# MCU.net
KiCad netlist of a schematic drawn in Altium Designer
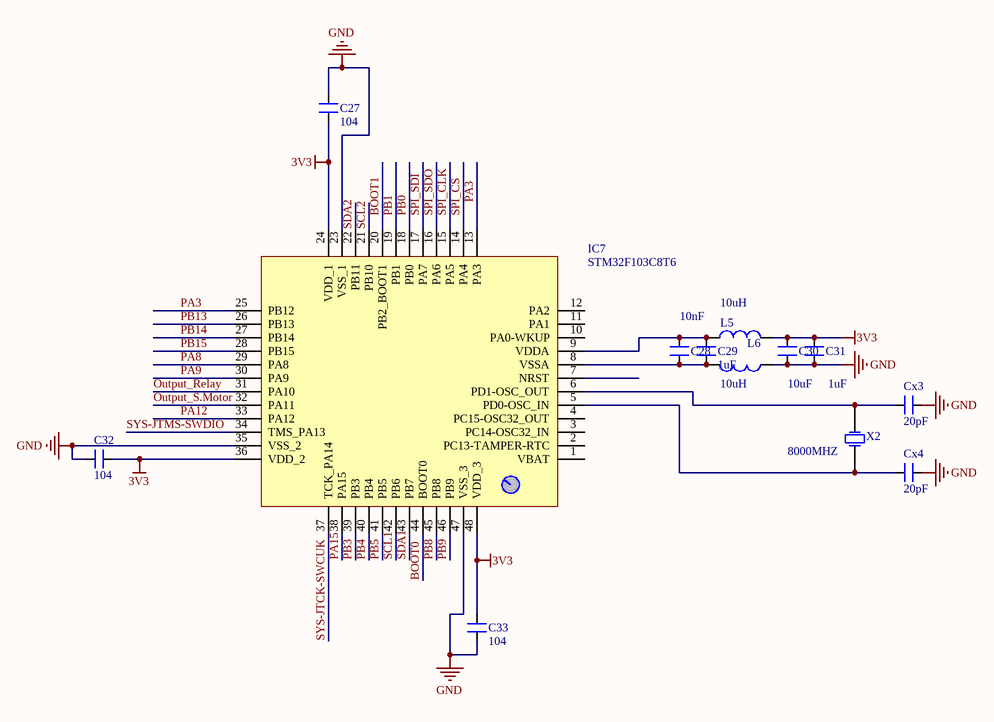
[diagram p0: MCU.SchDoc]

(export (version "E")
  (design (tool "Eeschema 10.0.6"))
  (components
    (comp (ref "C27")
      (value "104")
      (footprint "CN2")
      (description "Cap np 104 => 105pF")
      (libsource (lib "Compiled_Devzone") (part "CN2"))
    )
    (comp (ref "C28")
      (value "10nF")
      (footprint "CN2")
      (description "Cap np 104 => 105pF")
      (libsource (lib "Compiled_Devzone") (part "CN2"))
    )
    (comp (ref "C29")
      (value "1uF")
      (footprint "CN2")
      (description "Cap np 104 => 105pF")
      (libsource (lib "Compiled_Devzone") (part "CN2"))
    )
    (comp (ref "C30")
      (value "10uF")
      (footprint "CN2")
      (description "Cap np 104 => 105pF")
      (libsource (lib "Compiled_Devzone") (part "CN2"))
    )
    (comp (ref "C31")
      (value "1uF")
      (footprint "CN2")
      (description "Cap np 104 => 105pF")
      (libsource (lib "Compiled_Devzone") (part "CN2"))
    )
    (comp (ref "C32")
      (value "104")
      (footprint "CN2")
      (description "Cap np 104 => 105pF")
      (libsource (lib "Compiled_Devzone") (part "CN2"))
    )
    (comp (ref "C33")
      (value "104")
      (footprint "CN2")
      (description "Cap np 104 => 105pF")
      (libsource (lib "Compiled_Devzone") (part "CN2"))
    )
    (comp (ref "Cx3")
      (value "20pF")
      (footprint "CN1")
      (description "Cremic For Xtal 1pF => 100pF")
      (libsource (lib "Compiled_Devzone") (part "CN0"))
    )
    (comp (ref "Cx4")
      (value "20pF")
      (footprint "CN1")
      (description "Cremic For Xtal 1pF => 100pF")
      (libsource (lib "Compiled_Devzone") (part "CN0"))
    )
    (comp (ref "IC7")
      (value "STM32F103C8T6")
      (footprint "STM32F103C8T6")
      (libsource (lib "Compiled_Devzone") (part "STM32F103C8T6"))
    )
    (comp (ref "L5")
      (value "10uH")
      (footprint "L/0.4")
      (description "Inductor")
      (libsource (lib "Compiled_Devzone") (part "L1"))
    )
    (comp (ref "L6")
      (value "10uH")
      (footprint "L/0.4")
      (description "Inductor")
      (libsource (lib "Compiled_Devzone") (part "L1"))
    )
    (comp (ref "X2")
      (value "8000MHZ")
      (footprint "XTAL")
      (description "Crystal Oscillator")
      (fields (field (name "PUBLISHER") "Altium Limited"))
      (libsource (lib "hphonglib") (part "XTAL"))
    )
  )
  (nets
    (net (code "1") (name "/BOOT0") (class "Default")
      (node (ref "IC7") (pin "44") (pinfunction "BOOT0_44") (pintype "passive"))
    )
    (net (code "2") (name "/BOOT1") (class "Default")
      (node (ref "IC7") (pin "20") (pinfunction "PB2_BOOT1_20") (pintype "passive"))
    )
    (net (code "3") (name "/Output_Relay") (class "Default")
      (node (ref "IC7") (pin "31") (pinfunction "PA10_31") (pintype "passive"))
    )
    (net (code "4") (name "/Output_S.Motor") (class "Default")
      (node (ref "IC7") (pin "32") (pinfunction "PA11_32") (pintype "passive"))
    )
    (net (code "5") (name "/PA3") (class "Default")
      (node (ref "IC7") (pin "13") (pinfunction "PA3_13") (pintype "passive"))
      (node (ref "IC7") (pin "25") (pinfunction "PB12_25") (pintype "passive"))
    )
    (net (code "6") (name "/PA8") (class "Default")
      (node (ref "IC7") (pin "29") (pinfunction "PA8_29") (pintype "passive"))
    )
    (net (code "7") (name "/PA9") (class "Default")
      (node (ref "IC7") (pin "30") (pinfunction "PA9_30") (pintype "passive"))
    )
    (net (code "8") (name "/PA12") (class "Default")
      (node (ref "IC7") (pin "33") (pinfunction "PA12_33") (pintype "passive"))
    )
    (net (code "9") (name "/PA15") (class "Default")
      (node (ref "IC7") (pin "38") (pinfunction "PA15_38") (pintype "passive"))
    )
    (net (code "10") (name "/PB0") (class "Default")
      (node (ref "IC7") (pin "18") (pinfunction "PB0_18") (pintype "passive"))
    )
    (net (code "11") (name "/PB1") (class "Default")
      (node (ref "IC7") (pin "19") (pinfunction "PB1_19") (pintype "passive"))
    )
    (net (code "12") (name "/PB3") (class "Default")
      (node (ref "IC7") (pin "39") (pinfunction "PB3_39") (pintype "passive"))
    )
    (net (code "13") (name "/PB4") (class "Default")
      (node (ref "IC7") (pin "40") (pinfunction "PB4_40") (pintype "passive"))
    )
    (net (code "14") (name "/PB5") (class "Default")
      (node (ref "IC7") (pin "41") (pinfunction "PB5_41") (pintype "passive"))
    )
    (net (code "15") (name "/PB8") (class "Default")
      (node (ref "IC7") (pin "45") (pinfunction "PB8_45") (pintype "passive"))
    )
    (net (code "16") (name "/PB9") (class "Default")
      (node (ref "IC7") (pin "46") (pinfunction "PB9_46") (pintype "passive"))
    )
    (net (code "17") (name "/PB13") (class "Default")
      (node (ref "IC7") (pin "26") (pinfunction "PB13_26") (pintype "passive"))
    )
    (net (code "18") (name "/PB14") (class "Default")
      (node (ref "IC7") (pin "27") (pinfunction "PB14_27") (pintype "passive"))
    )
    (net (code "19") (name "/PB15") (class "Default")
      (node (ref "IC7") (pin "28") (pinfunction "PB15_28") (pintype "passive"))
    )
    (net (code "20") (name "/SCL1") (class "Default")
      (node (ref "IC7") (pin "42") (pinfunction "PB6_42") (pintype "passive"))
    )
    (net (code "21") (name "/SCL2") (class "Default")
      (node (ref "IC7") (pin "21") (pinfunction "PB10_21") (pintype "passive"))
    )
    (net (code "22") (name "/SDA1") (class "Default")
      (node (ref "IC7") (pin "43") (pinfunction "PB7_43") (pintype "passive"))
    )
    (net (code "23") (name "/SDA2") (class "Default")
      (node (ref "IC7") (pin "22") (pinfunction "PB11_22") (pintype "passive"))
    )
    (net (code "24") (name "/SPI_CLK") (class "Default")
      (node (ref "IC7") (pin "15") (pinfunction "PA5_15") (pintype "passive"))
    )
    (net (code "25") (name "/SPI_CS") (class "Default")
      (node (ref "IC7") (pin "14") (pinfunction "PA4_14") (pintype "passive"))
    )
    (net (code "26") (name "/SPI_SDI") (class "Default")
      (node (ref "IC7") (pin "17") (pinfunction "PA7_17") (pintype "passive"))
    )
    (net (code "27") (name "/SPI_SDO") (class "Default")
      (node (ref "IC7") (pin "16") (pinfunction "PA6_16") (pintype "passive"))
    )
    (net (code "28") (name "/SYS-JTCK-SWCUK") (class "Default")
      (node (ref "IC7") (pin "37") (pinfunction "TCK_PA14_37") (pintype "passive"))
    )
    (net (code "29") (name "/SYS-JTMS-SWDIO") (class "Default")
      (node (ref "IC7") (pin "34") (pinfunction "TMS_PA13_34") (pintype "passive"))
    )
    (net (code "30") (name "3V3") (class "Default")
      (node (ref "C27") (pin "1") (pinfunction "1_1") (pintype "passive"))
      (node (ref "C30") (pin "1") (pinfunction "1_1") (pintype "passive"))
      (node (ref "C31") (pin "1") (pinfunction "1_1") (pintype "passive"))
      (node (ref "C32") (pin "2") (pinfunction "2_2") (pintype "passive"))
      (node (ref "C33") (pin "2") (pinfunction "2_2") (pintype "passive"))
      (node (ref "IC7") (pin "24") (pinfunction "VDD_1_24") (pintype "passive"))
      (node (ref "IC7") (pin "36") (pinfunction "VDD_2_36") (pintype "passive"))
      (node (ref "IC7") (pin "48") (pinfunction "VDD_3_48") (pintype "passive"))
      (node (ref "L5") (pin "2") (pinfunction "2_2") (pintype "passive"))
    )
    (net (code "31") (name "GND") (class "Default")
      (node (ref "C27") (pin "2") (pinfunction "2_2") (pintype "passive"))
      (node (ref "C30") (pin "2") (pinfunction "2_2") (pintype "passive"))
      (node (ref "C31") (pin "2") (pinfunction "2_2") (pintype "passive"))
      (node (ref "C32") (pin "1") (pinfunction "1_1") (pintype "passive"))
      (node (ref "C33") (pin "1") (pinfunction "1_1") (pintype "passive"))
      (node (ref "Cx3") (pin "1") (pinfunction "1_1") (pintype "passive"))
      (node (ref "Cx4") (pin "1") (pinfunction "1_1") (pintype "passive"))
      (node (ref "IC7") (pin "23") (pinfunction "VSS_1_23") (pintype "passive"))
      (node (ref "IC7") (pin "35") (pinfunction "VSS_2_35") (pintype "passive"))
      (node (ref "IC7") (pin "47") (pinfunction "VSS_3_47") (pintype "passive"))
      (node (ref "L6") (pin "1") (pinfunction "1_1") (pintype "passive"))
    )
    (net (code "32") (name "Net-(IC7-PD0-OSC_IN)") (class "Default")
      (node (ref "Cx4") (pin "2") (pinfunction "2_2") (pintype "passive"))
      (node (ref "IC7") (pin "5") (pinfunction "PD0-OSC_IN_5") (pintype "passive"))
      (node (ref "X2") (pin "1") (pinfunction "OSC1_1") (pintype "passive"))
    )
    (net (code "33") (name "Net-(IC7-PD1-OSC_OUT)") (class "Default")
      (node (ref "Cx3") (pin "2") (pinfunction "2_2") (pintype "passive"))
      (node (ref "IC7") (pin "6") (pinfunction "PD1-OSC_OUT_6") (pintype "passive"))
      (node (ref "X2") (pin "2") (pinfunction "OSC2_2") (pintype "passive"))
    )
    (net (code "34") (name "Net-(IC7-VDDA)") (class "Default")
      (node (ref "C28") (pin "1") (pinfunction "1_1") (pintype "passive"))
      (node (ref "C29") (pin "1") (pinfunction "1_1") (pintype "passive"))
      (node (ref "IC7") (pin "9") (pinfunction "VDDA_9") (pintype "passive"))
      (node (ref "L5") (pin "1") (pinfunction "1_1") (pintype "passive"))
    )
    (net (code "35") (name "Net-(IC7-VSSA)") (class "Default")
      (node (ref "C28") (pin "2") (pinfunction "2_2") (pintype "passive"))
      (node (ref "C29") (pin "2") (pinfunction "2_2") (pintype "passive"))
      (node (ref "IC7") (pin "8") (pinfunction "VSSA_8") (pintype "passive"))
      (node (ref "L6") (pin "2") (pinfunction "2_2") (pintype "passive"))
    )
    (net (code "36") (name "unconnected-(IC7-NRST-Pad7)") (class "Default")
      (node (ref "IC7") (pin "7") (pinfunction "NRST_7") (pintype "passive"))
    )
    (net (code "37") (name "unconnected-(IC7-PA0-WKUP-Pad10)") (class "Default")
      (node (ref "IC7") (pin "10") (pinfunction "PA0-WKUP_10") (pintype "passive"))
    )
    (net (code "38") (name "unconnected-(IC7-PA1-Pad11)") (class "Default")
      (node (ref "IC7") (pin "11") (pinfunction "PA1_11") (pintype "passive"))
    )
    (net (code "39") (name "unconnected-(IC7-PA2-Pad12)") (class "Default")
      (node (ref "IC7") (pin "12") (pinfunction "PA2_12") (pintype "passive"))
    )
    (net (code "40") (name "unconnected-(IC7-PC13-TAMPER-RTC-Pad2)") (class "Default")
      (node (ref "IC7") (pin "2") (pinfunction "PC13-TAMPER-RTC_2") (pintype "passive"))
    )
    (net (code "41") (name "unconnected-(IC7-PC14-OSC32_IN-Pad3)") (class "Default")
      (node (ref "IC7") (pin "3") (pinfunction "PC14-OSC32_IN_3") (pintype "passive"))
    )
    (net (code "42") (name "unconnected-(IC7-PC15-OSC32_OUT-Pad4)") (class "Default")
      (node (ref "IC7") (pin "4") (pinfunction "PC15-OSC32_OUT_4") (pintype "passive"))
    )
    (net (code "43") (name "unconnected-(IC7-VBAT-Pad1)") (class "Default")
      (node (ref "IC7") (pin "1") (pinfunction "VBAT_1") (pintype "passive"))
    )
  )
)
